# car_sch.net
KiCad netlist of a schematic drawn in EAGLE
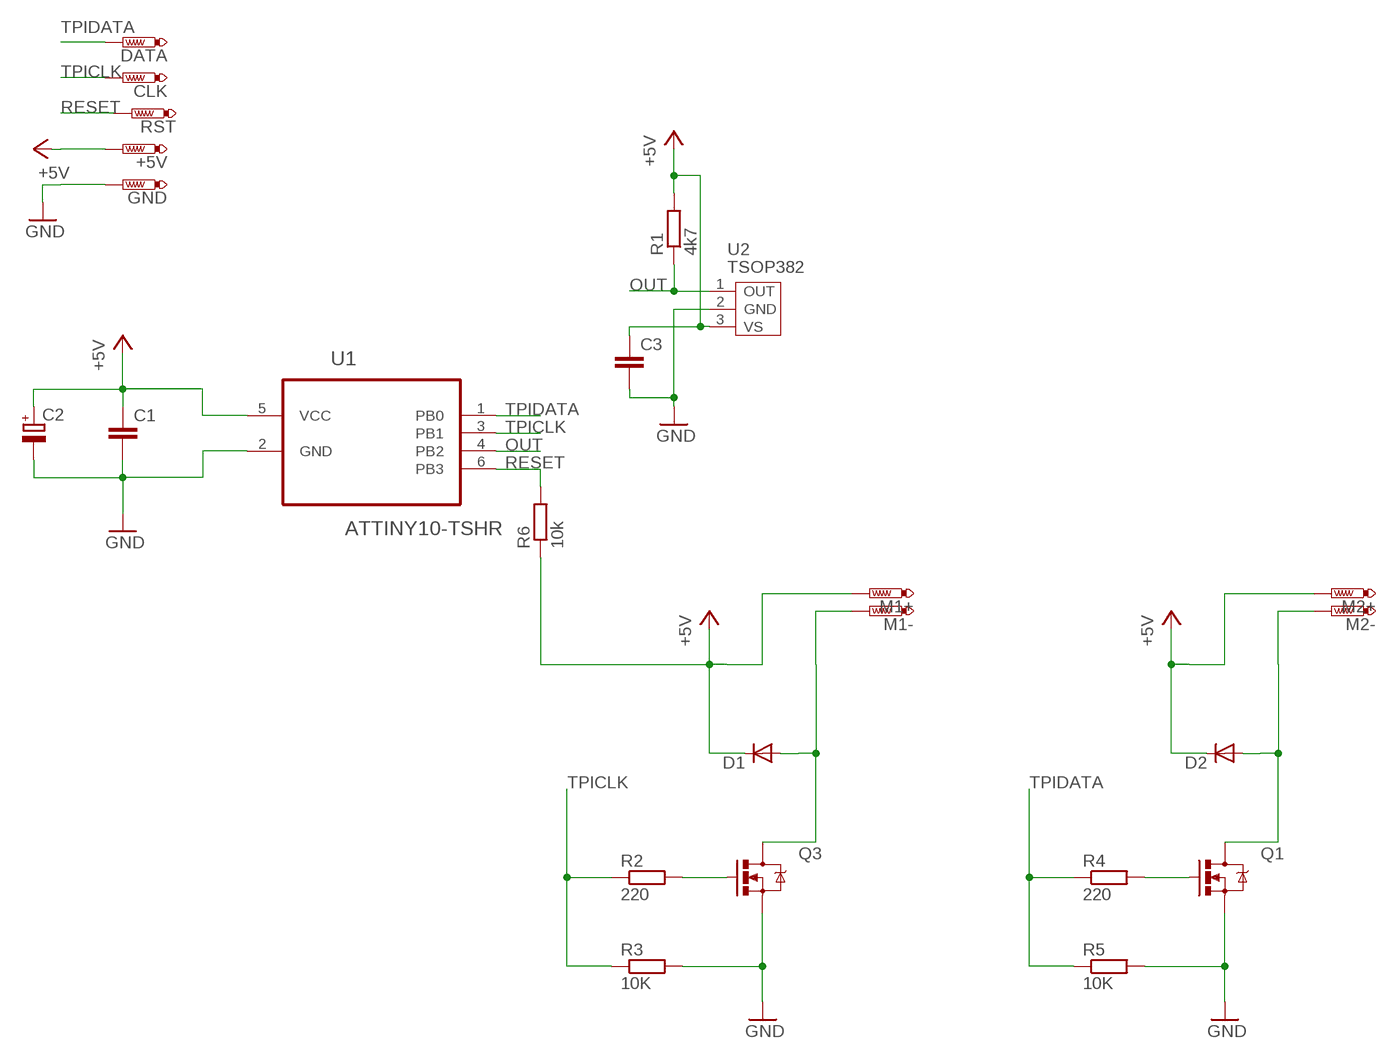
[diagram p0: schematic, sheet 1]

(export (version "E")
  (design (tool "Eeschema 10.0.6"))
  (components
    (comp (ref "+5V")
      (value "PTR1TP11R")
      (footprint "eagle-import:TP11R")
      (libsource (lib "eagle-import") (part "PTR1TP11R"))
    )
    (comp (ref "C1")
      (value "C-EUC0603")
      (footprint "eagle-import:C0603")
      (libsource (lib "eagle-import") (part "C-EUC0603"))
    )
    (comp (ref "C2")
      (value "CPOL-EUSMCA")
      (footprint "eagle-import:SMC_A")
      (libsource (lib "eagle-import") (part "CPOL-EUSMCA"))
    )
    (comp (ref "C3")
      (value "C-EUC0603")
      (footprint "eagle-import:C0603")
      (libsource (lib "eagle-import") (part "C-EUC0603"))
    )
    (comp (ref "CLK")
      (value "PTR1TP11R")
      (footprint "eagle-import:TP11R")
      (libsource (lib "eagle-import") (part "PTR1TP11R"))
    )
    (comp (ref "D1")
      (value "DIODESOD")
      (footprint "eagle-import:SOD-323")
      (libsource (lib "eagle-import") (part "DIODESOD"))
    )
    (comp (ref "D2")
      (value "DIODESOD")
      (footprint "eagle-import:SOD-323")
      (libsource (lib "eagle-import") (part "DIODESOD"))
    )
    (comp (ref "DATA")
      (value "PTR1TP11R")
      (footprint "eagle-import:TP11R")
      (libsource (lib "eagle-import") (part "PTR1TP11R"))
    )
    (comp (ref "GND")
      (value "PTR1TP11R")
      (footprint "eagle-import:TP11R")
      (libsource (lib "eagle-import") (part "PTR1TP11R"))
    )
    (comp (ref "M1+")
      (value "PTR1TP11R")
      (footprint "eagle-import:TP11R")
      (libsource (lib "eagle-import") (part "PTR1TP11R"))
    )
    (comp (ref "M1-")
      (value "PTR1TP11R")
      (footprint "eagle-import:TP11R")
      (libsource (lib "eagle-import") (part "PTR1TP11R"))
    )
    (comp (ref "M2+")
      (value "PTR1TP11R")
      (footprint "eagle-import:TP11R")
      (libsource (lib "eagle-import") (part "PTR1TP11R"))
    )
    (comp (ref "M2-")
      (value "PTR1TP11R")
      (footprint "eagle-import:TP11R")
      (libsource (lib "eagle-import") (part "PTR1TP11R"))
    )
    (comp (ref "Q1")
      (value "MOSFET-NCHANNELBSS123LT1G")
      (footprint "eagle-import:SOT23")
      (libsource (lib "eagle-import") (part "MOSFET-NCHANNELBSS123LT1G"))
    )
    (comp (ref "Q3")
      (value "MOSFET-NCHANNELBSS123LT1G")
      (footprint "eagle-import:SOT23")
      (libsource (lib "eagle-import") (part "MOSFET-NCHANNELBSS123LT1G"))
    )
    (comp (ref "R1")
      (value "4k7")
      (footprint "eagle-import:R0603")
      (libsource (lib "eagle-import") (part "R-EU_R0603"))
    )
    (comp (ref "R2")
      (value "220")
      (footprint "eagle-import:R0603")
      (libsource (lib "eagle-import") (part "R-EU_R0603"))
    )
    (comp (ref "R3")
      (value "10K")
      (footprint "eagle-import:R0603")
      (libsource (lib "eagle-import") (part "R-EU_R0603"))
    )
    (comp (ref "R4")
      (value "220")
      (footprint "eagle-import:R0603")
      (libsource (lib "eagle-import") (part "R-EU_R0603"))
    )
    (comp (ref "R5")
      (value "10K")
      (footprint "eagle-import:R0603")
      (libsource (lib "eagle-import") (part "R-EU_R0603"))
    )
    (comp (ref "R6")
      (value "10k")
      (footprint "eagle-import:R0603")
      (libsource (lib "eagle-import") (part "R-EU_R0603"))
    )
    (comp (ref "RST")
      (value "PTR1TP11R")
      (footprint "eagle-import:TP11R")
      (libsource (lib "eagle-import") (part "PTR1TP11R"))
    )
    (comp (ref "U1")
      (value "ATTINY10-TSHR")
      (footprint "eagle-import:SOT95P280X145-6N")
      (libsource (lib "eagle-import") (part "ATTINY10-TSHR"))
    )
    (comp (ref "U2")
      (value "TSOP382")
      (footprint "eagle-import:3P-2.54-4.8X5X6.95H")
      (libsource (lib "eagle-import") (part "TSOP382"))
    )
  )
  (nets
    (net (code "1") (name "+5V") (class "Default")
      (node (ref "+5V") (pin "TP") (pinfunction "TP_TP") (pintype "input"))
      (node (ref "C1") (pin "1") (pinfunction "1_1") (pintype "passive"))
      (node (ref "C2") (pin "+") (pinfunction "+_+") (pintype "passive"))
      (node (ref "C3") (pin "1") (pinfunction "1_1") (pintype "passive"))
      (node (ref "D1") (pin "1") (pinfunction "C_1") (pintype "passive"))
      (node (ref "D2") (pin "1") (pinfunction "C_1") (pintype "passive"))
      (node (ref "M1+") (pin "TP") (pinfunction "TP_TP") (pintype "input"))
      (node (ref "M2+") (pin "TP") (pinfunction "TP_TP") (pintype "input"))
      (node (ref "R1") (pin "2") (pinfunction "2_2") (pintype "passive"))
      (node (ref "R6") (pin "1") (pinfunction "1_1") (pintype "passive"))
      (node (ref "U1") (pin "5") (pinfunction "VCC_5") (pintype "power_in"))
      (node (ref "U2") (pin "3") (pinfunction "VS_3") (pintype "bidirectional"))
    )
    (net (code "2") (name "/OUT") (class "Default")
      (node (ref "R1") (pin "1") (pinfunction "1_1") (pintype "passive"))
      (node (ref "U1") (pin "4") (pinfunction "PB2_4") (pintype "bidirectional"))
      (node (ref "U2") (pin "1") (pinfunction "OUT_1") (pintype "bidirectional"))
    )
    (net (code "3") (name "/RESET") (class "Default")
      (node (ref "R6") (pin "2") (pinfunction "2_2") (pintype "passive"))
      (node (ref "RST") (pin "TP") (pinfunction "TP_TP") (pintype "input"))
      (node (ref "U1") (pin "6") (pinfunction "PB3_6") (pintype "bidirectional"))
    )
    (net (code "4") (name "/TPICLK") (class "Default")
      (node (ref "CLK") (pin "TP") (pinfunction "TP_TP") (pintype "input"))
      (node (ref "R2") (pin "1") (pinfunction "1_1") (pintype "passive"))
      (node (ref "R3") (pin "1") (pinfunction "1_1") (pintype "passive"))
      (node (ref "U1") (pin "3") (pinfunction "PB1_3") (pintype "bidirectional"))
    )
    (net (code "5") (name "/TPIDATA") (class "Default")
      (node (ref "DATA") (pin "TP") (pinfunction "TP_TP") (pintype "input"))
      (node (ref "R4") (pin "1") (pinfunction "1_1") (pintype "passive"))
      (node (ref "R5") (pin "1") (pinfunction "1_1") (pintype "passive"))
      (node (ref "U1") (pin "1") (pinfunction "PB0_1") (pintype "bidirectional"))
    )
    (net (code "6") (name "GND") (class "Default")
      (node (ref "C1") (pin "2") (pinfunction "2_2") (pintype "passive"))
      (node (ref "C2") (pin "-") (pinfunction "-_-") (pintype "passive"))
      (node (ref "C3") (pin "2") (pinfunction "2_2") (pintype "passive"))
      (node (ref "GND") (pin "TP") (pinfunction "TP_TP") (pintype "input"))
      (node (ref "Q1") (pin "2") (pinfunction "S_2") (pintype "passive"))
      (node (ref "Q3") (pin "2") (pinfunction "S_2") (pintype "passive"))
      (node (ref "R3") (pin "2") (pinfunction "2_2") (pintype "passive"))
      (node (ref "R5") (pin "2") (pinfunction "2_2") (pintype "passive"))
      (node (ref "U1") (pin "2") (pinfunction "GND_2") (pintype "passive"))
      (node (ref "U2") (pin "2") (pinfunction "GND_2") (pintype "bidirectional"))
    )
    (net (code "7") (name "Net-(D1-A)") (class "Default")
      (node (ref "D1") (pin "2") (pinfunction "A_2") (pintype "passive"))
      (node (ref "M1-") (pin "TP") (pinfunction "TP_TP") (pintype "input"))
      (node (ref "Q3") (pin "3") (pinfunction "D_3") (pintype "passive"))
    )
    (net (code "8") (name "Net-(D2-A)") (class "Default")
      (node (ref "D2") (pin "2") (pinfunction "A_2") (pintype "passive"))
      (node (ref "M2-") (pin "TP") (pinfunction "TP_TP") (pintype "input"))
      (node (ref "Q1") (pin "3") (pinfunction "D_3") (pintype "passive"))
    )
    (net (code "9") (name "Net-(Q1-G)") (class "Default")
      (node (ref "Q1") (pin "1") (pinfunction "G_1") (pintype "passive"))
      (node (ref "R4") (pin "2") (pinfunction "2_2") (pintype "passive"))
    )
    (net (code "10") (name "Net-(Q3-G)") (class "Default")
      (node (ref "Q3") (pin "1") (pinfunction "G_1") (pintype "passive"))
      (node (ref "R2") (pin "2") (pinfunction "2_2") (pintype "passive"))
    )
  )
)
